# Extension_S-E.net
KiCad netlist of a schematic drawn in EAGLE
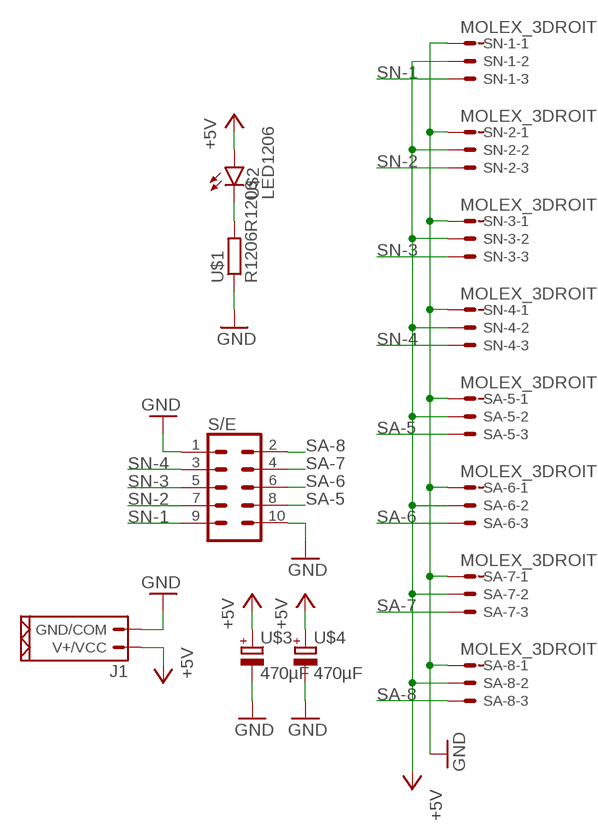
[diagram p0: schematic, sheet 1]

(export (version "E")
  (design (tool "Eeschema 10.0.6"))
  (components
    (comp (ref "J1")
      (value "MOLEX_2_PUISS90°")
      (footprint "eagle-import:CON_2_PUISS_90°")
      (libsource (lib "eagle-import") (part "MOLEX_2_PUISS90°"))
    )
    (comp (ref "S/E")
      (value "CON_5X2SHD")
      (footprint "eagle-import:2X5-SHROUDED")
      (libsource (lib "eagle-import") (part "CON_5X2SHD"))
    )
    (comp (ref "SA-5")
      (value "MOLEX_3DROIT")
      (footprint "eagle-import:CON_3_DROIT")
      (fields (field (name "MF") "MOLEX"))
      (libsource (lib "eagle-import") (part "MOLEX_3DROIT"))
    )
    (comp (ref "SA-6")
      (value "MOLEX_3DROIT")
      (footprint "eagle-import:CON_3_DROIT")
      (fields (field (name "MF") "MOLEX"))
      (libsource (lib "eagle-import") (part "MOLEX_3DROIT"))
    )
    (comp (ref "SA-7")
      (value "MOLEX_3DROIT")
      (footprint "eagle-import:CON_3_DROIT")
      (fields (field (name "MF") "MOLEX"))
      (libsource (lib "eagle-import") (part "MOLEX_3DROIT"))
    )
    (comp (ref "SA-8")
      (value "MOLEX_3DROIT")
      (footprint "eagle-import:CON_3_DROIT")
      (fields (field (name "MF") "MOLEX"))
      (libsource (lib "eagle-import") (part "MOLEX_3DROIT"))
    )
    (comp (ref "SN-1")
      (value "MOLEX_3DROIT")
      (footprint "eagle-import:CON_3_DROIT")
      (fields (field (name "MF") "MOLEX"))
      (libsource (lib "eagle-import") (part "MOLEX_3DROIT"))
    )
    (comp (ref "SN-2")
      (value "MOLEX_3DROIT")
      (footprint "eagle-import:CON_3_DROIT")
      (fields (field (name "MF") "MOLEX"))
      (libsource (lib "eagle-import") (part "MOLEX_3DROIT"))
    )
    (comp (ref "SN-3")
      (value "MOLEX_3DROIT")
      (footprint "eagle-import:CON_3_DROIT")
      (fields (field (name "MF") "MOLEX"))
      (libsource (lib "eagle-import") (part "MOLEX_3DROIT"))
    )
    (comp (ref "SN-4")
      (value "MOLEX_3DROIT")
      (footprint "eagle-import:CON_3_DROIT")
      (fields (field (name "MF") "MOLEX"))
      (libsource (lib "eagle-import") (part "MOLEX_3DROIT"))
    )
    (comp (ref "U$1")
      (value "R1206R1206")
      (footprint "eagle-import:R1206")
      (libsource (lib "eagle-import") (part "R1206R1206"))
    )
    (comp (ref "U$2")
      (value "LED1206")
      (footprint "eagle-import:1206")
      (libsource (lib "eagle-import") (part "LED1206"))
    )
    (comp (ref "U$3")
      (value "470µF")
      (footprint "eagle-import:E3,5-8")
      (libsource (lib "eagle-import") (part "CONDO3.5-8"))
    )
    (comp (ref "U$4")
      (value "470µF")
      (footprint "eagle-import:E3,5-8")
      (libsource (lib "eagle-import") (part "CONDO3.5-8"))
    )
  )
  (nets
    (net (code "1") (name "+5V") (class "Default")
      (node (ref "J1") (pin "P$2") (pinfunction "V+/VCC_P$2") (pintype "passive"))
      (node (ref "SA-5") (pin "2") (pinfunction "S_2") (pintype "passive"))
      (node (ref "SA-6") (pin "2") (pinfunction "S_2") (pintype "passive"))
      (node (ref "SA-7") (pin "2") (pinfunction "S_2") (pintype "passive"))
      (node (ref "SA-8") (pin "2") (pinfunction "S_2") (pintype "passive"))
      (node (ref "SN-1") (pin "2") (pinfunction "S_2") (pintype "passive"))
      (node (ref "SN-2") (pin "2") (pinfunction "S_2") (pintype "passive"))
      (node (ref "SN-3") (pin "2") (pinfunction "S_2") (pintype "passive"))
      (node (ref "SN-4") (pin "2") (pinfunction "S_2") (pintype "passive"))
      (node (ref "U$2") (pin "A") (pinfunction "A_A") (pintype "passive"))
      (node (ref "U$3") (pin "+") (pinfunction "+_+") (pintype "passive"))
      (node (ref "U$4") (pin "+") (pinfunction "+_+") (pintype "passive"))
    )
    (net (code "2") (name "/SA-5") (class "Default")
      (node (ref "S/E") (pin "8") (pinfunction "8_8") (pintype "passive"))
      (node (ref "SA-5") (pin "3") (pinfunction "S_3") (pintype "passive"))
    )
    (net (code "3") (name "/SA-6") (class "Default")
      (node (ref "S/E") (pin "6") (pinfunction "6_6") (pintype "passive"))
      (node (ref "SA-6") (pin "3") (pinfunction "S_3") (pintype "passive"))
    )
    (net (code "4") (name "/SA-7") (class "Default")
      (node (ref "S/E") (pin "4") (pinfunction "4_4") (pintype "passive"))
      (node (ref "SA-7") (pin "3") (pinfunction "S_3") (pintype "passive"))
    )
    (net (code "5") (name "/SA-8") (class "Default")
      (node (ref "S/E") (pin "2") (pinfunction "2_2") (pintype "passive"))
      (node (ref "SA-8") (pin "3") (pinfunction "S_3") (pintype "passive"))
    )
    (net (code "6") (name "/SN-1") (class "Default")
      (node (ref "S/E") (pin "9") (pinfunction "9_9") (pintype "passive"))
      (node (ref "SN-1") (pin "3") (pinfunction "S_3") (pintype "passive"))
    )
    (net (code "7") (name "/SN-2") (class "Default")
      (node (ref "S/E") (pin "7") (pinfunction "7_7") (pintype "passive"))
      (node (ref "SN-2") (pin "3") (pinfunction "S_3") (pintype "passive"))
    )
    (net (code "8") (name "/SN-3") (class "Default")
      (node (ref "S/E") (pin "5") (pinfunction "5_5") (pintype "passive"))
      (node (ref "SN-3") (pin "3") (pinfunction "S_3") (pintype "passive"))
    )
    (net (code "9") (name "/SN-4") (class "Default")
      (node (ref "S/E") (pin "3") (pinfunction "3_3") (pintype "passive"))
      (node (ref "SN-4") (pin "3") (pinfunction "S_3") (pintype "passive"))
    )
    (net (code "10") (name "GND") (class "Default")
      (node (ref "J1") (pin "P$1") (pinfunction "GND/COM_P$1") (pintype "passive"))
      (node (ref "S/E") (pin "1") (pinfunction "1_1") (pintype "passive"))
      (node (ref "S/E") (pin "10") (pinfunction "10_10") (pintype "passive"))
      (node (ref "SA-5") (pin "1") (pinfunction "S_1") (pintype "passive"))
      (node (ref "SA-6") (pin "1") (pinfunction "S_1") (pintype "passive"))
      (node (ref "SA-7") (pin "1") (pinfunction "S_1") (pintype "passive"))
      (node (ref "SA-8") (pin "1") (pinfunction "S_1") (pintype "passive"))
      (node (ref "SN-1") (pin "1") (pinfunction "S_1") (pintype "passive"))
      (node (ref "SN-2") (pin "1") (pinfunction "S_1") (pintype "passive"))
      (node (ref "SN-3") (pin "1") (pinfunction "S_1") (pintype "passive"))
      (node (ref "SN-4") (pin "1") (pinfunction "S_1") (pintype "passive"))
      (node (ref "U$1") (pin "1") (pinfunction "1_1") (pintype "passive"))
      (node (ref "U$3") (pin "-") (pinfunction "-_-") (pintype "passive"))
      (node (ref "U$4") (pin "-") (pinfunction "-_-") (pintype "passive"))
    )
    (net (code "11") (name "Net-(U$1-Pad2)") (class "Default")
      (node (ref "U$1") (pin "2") (pinfunction "2_2") (pintype "passive"))
      (node (ref "U$2") (pin "C") (pinfunction "C_C") (pintype "passive"))
    )
  )
)
